# senseBox-BME680_v20.net
KiCad netlist of a schematic drawn in EAGLE
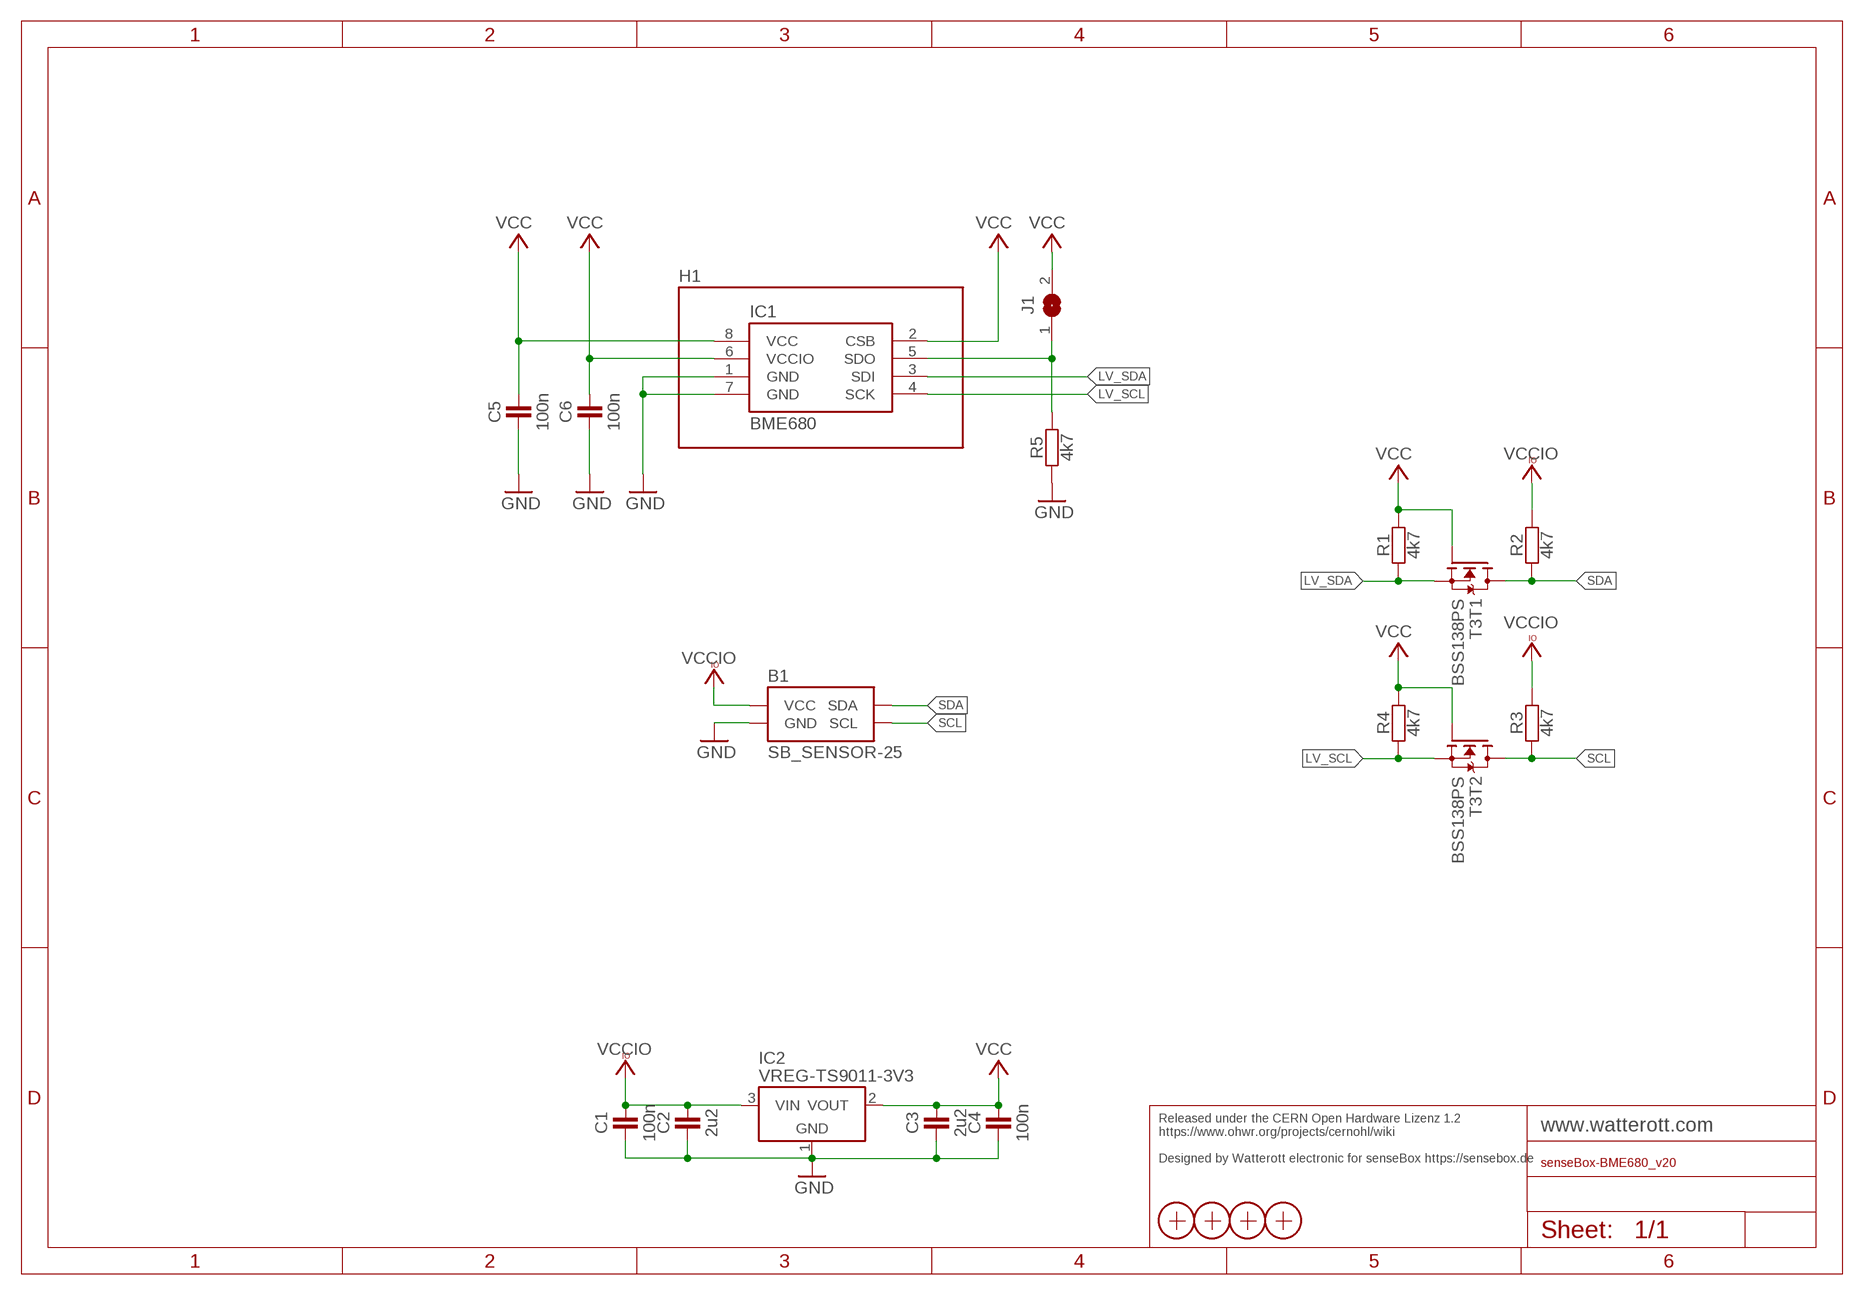
[diagram p0: schematic, sheet 1]

(export (version "E")
  (design (tool "Eeschema 10.0.6"))
  (components
    (comp (ref "B1")
      (value "SB_SENSOR-25")
      (footprint "eagle-import:SB-25X25")
      (libsource (lib "eagle-import") (part "SB_SENSOR-25"))
    )
    (comp (ref "C1")
      (value "100n")
      (footprint "eagle-import:C0402")
      (libsource (lib "eagle-import") (part "CAPACITOR-0402"))
    )
    (comp (ref "C2")
      (value "2u2")
      (footprint "eagle-import:C0402")
      (libsource (lib "eagle-import") (part "CAPACITOR-0402"))
    )
    (comp (ref "C3")
      (value "2u2")
      (footprint "eagle-import:C0402")
      (libsource (lib "eagle-import") (part "CAPACITOR-0402"))
    )
    (comp (ref "C4")
      (value "100n")
      (footprint "eagle-import:C0402")
      (libsource (lib "eagle-import") (part "CAPACITOR-0402"))
    )
    (comp (ref "C5")
      (value "100n")
      (footprint "eagle-import:C0402")
      (libsource (lib "eagle-import") (part "CAPACITOR-0402"))
    )
    (comp (ref "C6")
      (value "100n")
      (footprint "eagle-import:C0402")
      (libsource (lib "eagle-import") (part "CAPACITOR-0402"))
    )
    (comp (ref "H1")
      (value "SF2")
      (footprint "eagle-import:SF2")
      (libsource (lib "eagle-import") (part "SF2"))
    )
    (comp (ref "IC1")
      (value "BME680")
      (footprint "eagle-import:BME680")
      (libsource (lib "eagle-import") (part "BME680"))
    )
    (comp (ref "IC2")
      (value "VREG-TS9011-3V3")
      (footprint "eagle-import:SOT23")
      (libsource (lib "eagle-import") (part "VREG-TS9011-3V3"))
    )
    (comp (ref "J1")
      (value "JUMPER2-0402-NC")
      (footprint "eagle-import:JUMPER2-0402_NC")
      (libsource (lib "eagle-import") (part "JUMPER2-0402-NC"))
    )
    (comp (ref "R1")
      (value "4k7")
      (footprint "eagle-import:C0402")
      (libsource (lib "eagle-import") (part "RESISTOR-0402"))
    )
    (comp (ref "R2")
      (value "4k7")
      (footprint "eagle-import:C0402")
      (libsource (lib "eagle-import") (part "RESISTOR-0402"))
    )
    (comp (ref "R3")
      (value "4k7")
      (footprint "eagle-import:C0402")
      (libsource (lib "eagle-import") (part "RESISTOR-0402"))
    )
    (comp (ref "R4")
      (value "4k7")
      (footprint "eagle-import:C0402")
      (libsource (lib "eagle-import") (part "RESISTOR-0402"))
    )
    (comp (ref "R5")
      (value "4k7")
      (footprint "eagle-import:C0402")
      (libsource (lib "eagle-import") (part "RESISTOR-0402"))
    )
    (comp (ref "T3")
      (value "BSS138PS")
      (footprint "eagle-import:SOT363")
      (libsource (lib "eagle-import") (part "BSS138PS"))
    )
    (comp (ref "X1")
      (value "PASSER-07")
      (footprint "eagle-import:PASSER_07MM")
      (libsource (lib "eagle-import") (part "PASSER-07"))
    )
    (comp (ref "X2")
      (value "PASSER-07")
      (footprint "eagle-import:PASSER_07MM")
      (libsource (lib "eagle-import") (part "PASSER-07"))
    )
    (comp (ref "X3")
      (value "PASSER-07")
      (footprint "eagle-import:PASSER_07MM")
      (libsource (lib "eagle-import") (part "PASSER-07"))
    )
    (comp (ref "X4")
      (value "PASSER-07")
      (footprint "eagle-import:PASSER_07MM")
      (libsource (lib "eagle-import") (part "PASSER-07"))
    )
  )
  (nets
    (net (code "1") (name "GND") (class "Default")
      (node (ref "B1") (pin "GND") (pinfunction "GND_GND") (pintype "power_in"))
      (node (ref "C1") (pin "1") (pinfunction "1_1") (pintype "passive"))
      (node (ref "C2") (pin "1") (pinfunction "1_1") (pintype "passive"))
      (node (ref "C3") (pin "1") (pinfunction "1_1") (pintype "passive"))
      (node (ref "C4") (pin "1") (pinfunction "1_1") (pintype "passive"))
      (node (ref "C5") (pin "1") (pinfunction "1_1") (pintype "passive"))
      (node (ref "C6") (pin "1") (pinfunction "1_1") (pintype "passive"))
      (node (ref "IC1") (pin "1") (pinfunction "GND_1") (pintype "power_in"))
      (node (ref "IC1") (pin "7") (pinfunction "GND_7") (pintype "power_in"))
      (node (ref "IC2") (pin "1") (pinfunction "GND_1") (pintype "power_in"))
      (node (ref "R5") (pin "1") (pinfunction "1_1") (pintype "passive"))
    )
    (net (code "2") (name "LV_SCL") (class "Default")
      (node (ref "IC1") (pin "4") (pinfunction "SCK_4") (pintype "bidirectional"))
      (node (ref "R4") (pin "1") (pinfunction "1_1") (pintype "passive"))
      (node (ref "T3") (pin "4") (pinfunction "S_4") (pintype "passive"))
    )
    (net (code "3") (name "LV_SDA") (class "Default")
      (node (ref "IC1") (pin "3") (pinfunction "SDI_3") (pintype "bidirectional"))
      (node (ref "R1") (pin "1") (pinfunction "1_1") (pintype "passive"))
      (node (ref "T3") (pin "1") (pinfunction "S_1") (pintype "passive"))
    )
    (net (code "4") (name "Net-(IC1-SDO)") (class "Default")
      (node (ref "IC1") (pin "5") (pinfunction "SDO_5") (pintype "bidirectional"))
      (node (ref "J1") (pin "1") (pinfunction "1_1") (pintype "passive"))
      (node (ref "R5") (pin "2") (pinfunction "2_2") (pintype "passive"))
    )
    (net (code "5") (name "SCL") (class "Default")
      (node (ref "B1") (pin "SCL") (pinfunction "SCL_SCL") (pintype "bidirectional"))
      (node (ref "R3") (pin "1") (pinfunction "1_1") (pintype "passive"))
      (node (ref "T3") (pin "3") (pinfunction "D_3") (pintype "passive"))
    )
    (net (code "6") (name "SDA") (class "Default")
      (node (ref "B1") (pin "SDA") (pinfunction "SDA_SDA") (pintype "bidirectional"))
      (node (ref "R2") (pin "1") (pinfunction "1_1") (pintype "passive"))
      (node (ref "T3") (pin "6") (pinfunction "D_6") (pintype "passive"))
    )
    (net (code "7") (name "VCC") (class "Default")
      (node (ref "C3") (pin "2") (pinfunction "2_2") (pintype "passive"))
      (node (ref "C4") (pin "2") (pinfunction "2_2") (pintype "passive"))
      (node (ref "C5") (pin "2") (pinfunction "2_2") (pintype "passive"))
      (node (ref "C6") (pin "2") (pinfunction "2_2") (pintype "passive"))
      (node (ref "IC1") (pin "2") (pinfunction "CSB_2") (pintype "input"))
      (node (ref "IC1") (pin "6") (pinfunction "VCCIO_6") (pintype "power_in"))
      (node (ref "IC1") (pin "8") (pinfunction "VCC_8") (pintype "power_in"))
      (node (ref "IC2") (pin "2") (pinfunction "VOUT_2") (pintype "power_in"))
      (node (ref "J1") (pin "2") (pinfunction "2_2") (pintype "passive"))
      (node (ref "R1") (pin "2") (pinfunction "2_2") (pintype "passive"))
      (node (ref "R4") (pin "2") (pinfunction "2_2") (pintype "passive"))
      (node (ref "T3") (pin "2") (pinfunction "G_2") (pintype "passive"))
      (node (ref "T3") (pin "5") (pinfunction "G_5") (pintype "passive"))
    )
    (net (code "8") (name "VCCIO") (class "Default")
      (node (ref "B1") (pin "VCC") (pinfunction "VCC_VCC") (pintype "power_in"))
      (node (ref "C1") (pin "2") (pinfunction "2_2") (pintype "passive"))
      (node (ref "C2") (pin "2") (pinfunction "2_2") (pintype "passive"))
      (node (ref "IC2") (pin "3") (pinfunction "VIN_3") (pintype "power_in"))
      (node (ref "R2") (pin "2") (pinfunction "2_2") (pintype "passive"))
      (node (ref "R3") (pin "2") (pinfunction "2_2") (pintype "passive"))
    )
  )
)
